# Combo_miniUSB_TTL_v0_1.net
KiCad netlist of a schematic drawn in EAGLE
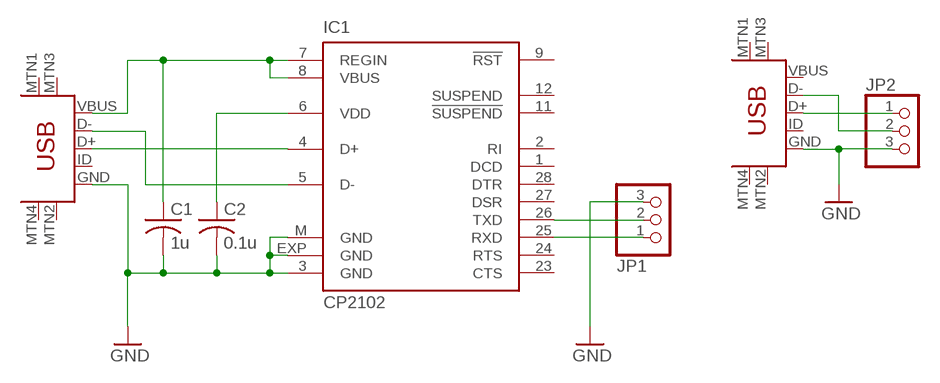
[diagram p0: schematic, sheet 1]

(export (version "E")
  (design (tool "Eeschema 10.0.6"))
  (components
    (comp (ref "C1")
      (value "1u")
      (footprint "eagle-import:C0805")
      (libsource (lib "eagle-import") (part "C-USC0805"))
    )
    (comp (ref "C2")
      (value "0.1u")
      (footprint "eagle-import:C0805")
      (libsource (lib "eagle-import") (part "C-USC0805"))
    )
    (comp (ref "IC1")
      (value "CP2102")
      (footprint "eagle-import:MLP28")
      (libsource (lib "eagle-import") (part "CP210X_USB_UART"))
    )
    (comp (ref "JP1")
      (value "PINHD-1X3")
      (footprint "eagle-import:1X03")
      (libsource (lib "eagle-import") (part "PINHD-1X3"))
    )
    (comp (ref "JP2")
      (value "PINHD-1X3")
      (footprint "eagle-import:1X03")
      (libsource (lib "eagle-import") (part "PINHD-1X3"))
    )
    (comp (ref "X1")
      (value "USB-MINIB-5PIN")
      (footprint "eagle-import:USB-MINIB")
      (libsource (lib "eagle-import") (part "SparkFun-Connectors_USB-MINIB-5PIN"))
    )
    (comp (ref "X2")
      (value "USB-MINIB-5PIN")
      (footprint "eagle-import:USB-MINIB")
      (libsource (lib "eagle-import") (part "USB-MINIB-5PIN"))
    )
  )
  (nets
    (net (code "1") (name "GND") (class "Default")
      (node (ref "C1") (pin "2") (pinfunction "2_2") (pintype "passive"))
      (node (ref "C2") (pin "2") (pinfunction "2_2") (pintype "passive"))
      (node (ref "IC1") (pin "3") (pinfunction "GND_3") (pintype "power_in"))
      (node (ref "IC1") (pin "EXP") (pinfunction "GND_EXP") (pintype "power_in"))
      (node (ref "IC1") (pin "M") (pinfunction "GND_M") (pintype "power_in"))
      (node (ref "JP1") (pin "3") (pinfunction "3_3") (pintype "passive"))
      (node (ref "JP2") (pin "3") (pinfunction "3_3") (pintype "passive"))
      (node (ref "X1") (pin "GND") (pinfunction "GND_GND") (pintype "bidirectional"))
      (node (ref "X2") (pin "GND") (pinfunction "GND_GND") (pintype "bidirectional"))
    )
    (net (code "2") (name "Net-(IC1-D+)") (class "Default")
      (node (ref "IC1") (pin "4") (pinfunction "D+_4") (pintype "bidirectional"))
      (node (ref "X2") (pin "D+") (pinfunction "D+_D+") (pintype "bidirectional"))
    )
    (net (code "3") (name "Net-(IC1-D-)") (class "Default")
      (node (ref "IC1") (pin "5") (pinfunction "D-_5") (pintype "bidirectional"))
      (node (ref "X2") (pin "D-") (pinfunction "D-_D-") (pintype "bidirectional"))
    )
    (net (code "4") (name "Net-(IC1-REGIN)") (class "Default")
      (node (ref "C1") (pin "1") (pinfunction "1_1") (pintype "passive"))
      (node (ref "IC1") (pin "7") (pinfunction "REGIN_7") (pintype "passive"))
      (node (ref "IC1") (pin "8") (pinfunction "VBUS_8") (pintype "input"))
      (node (ref "X2") (pin "VBUS") (pinfunction "VBUS_VBUS") (pintype "bidirectional"))
    )
    (net (code "5") (name "Net-(IC1-RXD)") (class "Default")
      (node (ref "IC1") (pin "25") (pinfunction "RXD_25") (pintype "input"))
      (node (ref "JP1") (pin "1") (pinfunction "1_1") (pintype "passive"))
    )
    (net (code "6") (name "Net-(IC1-TXD)") (class "Default")
      (node (ref "IC1") (pin "26") (pinfunction "TXD_26") (pintype "output"))
      (node (ref "JP1") (pin "2") (pinfunction "2_2") (pintype "passive"))
    )
    (net (code "7") (name "Net-(IC1-VDD)") (class "Default")
      (node (ref "C2") (pin "1") (pinfunction "1_1") (pintype "passive"))
      (node (ref "IC1") (pin "6") (pinfunction "VDD_6") (pintype "power_in"))
    )
    (net (code "8") (name "Net-(JP2-Pad1)") (class "Default")
      (node (ref "JP2") (pin "1") (pinfunction "1_1") (pintype "passive"))
      (node (ref "X1") (pin "D+") (pinfunction "D+_D+") (pintype "bidirectional"))
    )
    (net (code "9") (name "Net-(JP2-Pad2)") (class "Default")
      (node (ref "JP2") (pin "2") (pinfunction "2_2") (pintype "passive"))
      (node (ref "X1") (pin "D-") (pinfunction "D-_D-") (pintype "bidirectional"))
    )
    (net (code "10") (name "unconnected-(IC1-CTS-Pad23)") (class "Default")
      (node (ref "IC1") (pin "23") (pinfunction "CTS_23") (pintype "input"))
    )
    (net (code "11") (name "unconnected-(IC1-DCD-Pad1)") (class "Default")
      (node (ref "IC1") (pin "1") (pinfunction "DCD_1") (pintype "input"))
    )
    (net (code "12") (name "unconnected-(IC1-DSR-Pad27)") (class "Default")
      (node (ref "IC1") (pin "27") (pinfunction "DSR_27") (pintype "input"))
    )
    (net (code "13") (name "unconnected-(IC1-DTR-Pad28)") (class "Default")
      (node (ref "IC1") (pin "28") (pinfunction "DTR_28") (pintype "output"))
    )
    (net (code "14") (name "unconnected-(IC1-RI-Pad2)") (class "Default")
      (node (ref "IC1") (pin "2") (pinfunction "RI_2") (pintype "input"))
    )
    (net (code "15") (name "unconnected-(IC1-RTS-Pad24)") (class "Default")
      (node (ref "IC1") (pin "24") (pinfunction "RTS_24") (pintype "output"))
    )
    (net (code "16") (name "unconnected-(IC1-SUSPEND-Pad12)") (class "Default")
      (node (ref "IC1") (pin "12") (pinfunction "SUSPEND_12") (pintype "output"))
    )
    (net (code "17") (name "unconnected-(IC1-~{RST}-Pad9)") (class "Default")
      (node (ref "IC1") (pin "9") (pinfunction "~{RST}_9") (pintype "bidirectional"))
    )
    (net (code "18") (name "unconnected-(IC1-~{SUSPEND}-Pad11)") (class "Default")
      (node (ref "IC1") (pin "11") (pinfunction "~{SUSPEND}_11") (pintype "output"))
    )
    (net (code "19") (name "unconnected-(X1-MTN1-PadMTN3)") (class "Default")
      (node (ref "X1") (pin "MTN3") (pinfunction "MTN1_MTN3") (pintype "bidirectional"))
    )
    (net (code "20") (name "unconnected-(X1-MTN2-PadMTN1)") (class "Default")
      (node (ref "X1") (pin "MTN1") (pinfunction "MTN2_MTN1") (pintype "bidirectional"))
    )
    (net (code "21") (name "unconnected-(X1-MTN3-PadMTN2)") (class "Default")
      (node (ref "X1") (pin "MTN2") (pinfunction "MTN3_MTN2") (pintype "bidirectional"))
    )
    (net (code "22") (name "unconnected-(X1-PadID)") (class "Default")
      (node (ref "X1") (pin "ID") (pinfunction "ID_ID") (pintype "bidirectional"))
    )
    (net (code "23") (name "unconnected-(X1-PadMTN4)") (class "Default")
      (node (ref "X1") (pin "MTN4") (pinfunction "MTN4_MTN4") (pintype "bidirectional"))
    )
    (net (code "24") (name "unconnected-(X1-PadVBUS)") (class "Default")
      (node (ref "X1") (pin "VBUS") (pinfunction "VBUS_VBUS") (pintype "bidirectional"))
    )
    (net (code "25") (name "unconnected-(X2-MTN1-PadMTN3)") (class "Default")
      (node (ref "X2") (pin "MTN3") (pinfunction "MTN1_MTN3") (pintype "bidirectional"))
    )
    (net (code "26") (name "unconnected-(X2-MTN2-PadMTN1)") (class "Default")
      (node (ref "X2") (pin "MTN1") (pinfunction "MTN2_MTN1") (pintype "bidirectional"))
    )
    (net (code "27") (name "unconnected-(X2-MTN3-PadMTN2)") (class "Default")
      (node (ref "X2") (pin "MTN2") (pinfunction "MTN3_MTN2") (pintype "bidirectional"))
    )
    (net (code "28") (name "unconnected-(X2-PadID)") (class "Default")
      (node (ref "X2") (pin "ID") (pinfunction "ID_ID") (pintype "bidirectional"))
    )
    (net (code "29") (name "unconnected-(X2-PadMTN4)") (class "Default")
      (node (ref "X2") (pin "MTN4") (pinfunction "MTN4_MTN4") (pintype "bidirectional"))
    )
  )
)
